# Sensors.net
KiCad netlist of a schematic drawn in Altium Designer
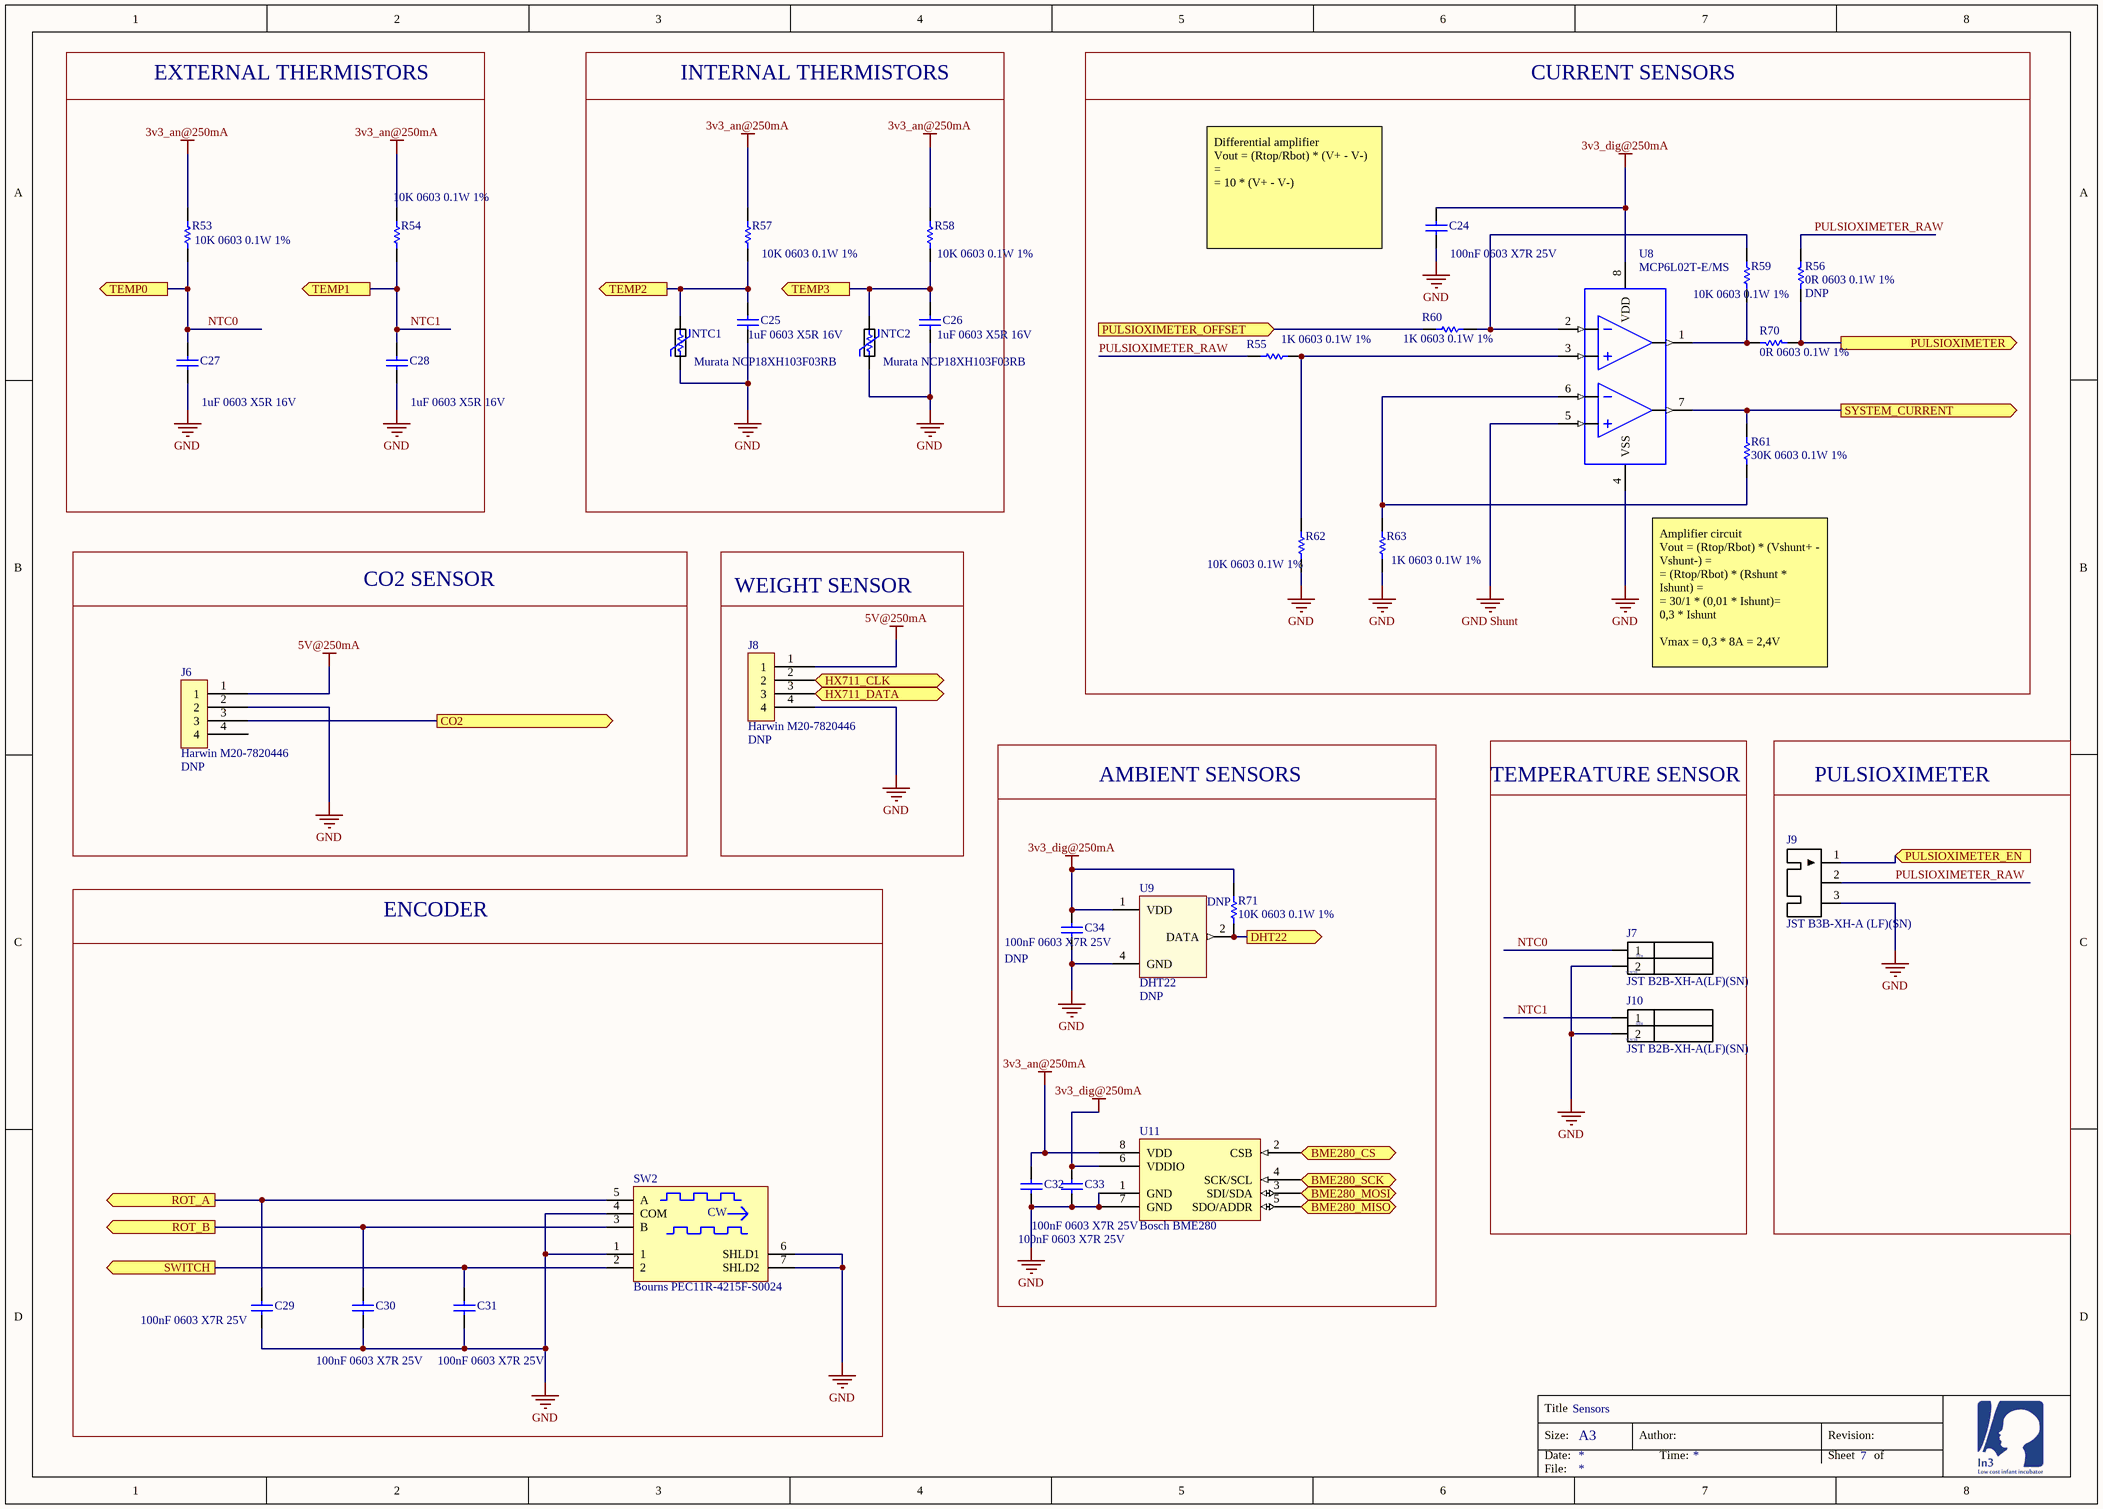
[diagram p0: Sensors.SchDoc]

(export (version "E")
  (design (tool "Eeschema 10.0.6"))
  (components
    (comp (ref "C24")
      (value "100nF 0603 X7R 25V")
      (footprint "CAPC1608X60X35NL10T15")
      (libsource (lib "CommunityVault") (part "CMP-c41a0d2b65641bdd-3"))
    )
    (comp (ref "C25")
      (value "1uF 0603 X5R 16V")
      (footprint "CAPC1608X60X35NL10T15")
      (fields (field (name "MANUFACTURER PART NUMBER") "GRM185R61C105KE44D"))
      (libsource (lib "CommunityVault") (part "CMP-119984-2"))
    )
    (comp (ref "C26")
      (value "1uF 0603 X5R 16V")
      (footprint "CAPC1608X60X35NL10T15")
      (fields (field (name "MANUFACTURER PART NUMBER") "GRM185R61C105KE44D"))
      (libsource (lib "CommunityVault") (part "CMP-119984-2"))
    )
    (comp (ref "C27")
      (value "1uF 0603 X5R 16V")
      (footprint "CAPC1608X60X35NL10T15")
      (fields (field (name "MANUFACTURER PART NUMBER") "GRM185R61C105KE44D"))
      (libsource (lib "CommunityVault") (part "CMP-119984-2"))
    )
    (comp (ref "C28")
      (value "1uF 0603 X5R 16V")
      (footprint "CAPC1608X60X35NL10T15")
      (fields (field (name "MANUFACTURER PART NUMBER") "GRM185R61C105KE44D"))
      (libsource (lib "CommunityVault") (part "CMP-119984-2"))
    )
    (comp (ref "C29")
      (value "100nF 0603 X7R 25V")
      (footprint "CAPC1608X60X35NL10T15")
      (libsource (lib "CommunityVault") (part "CMP-c41a0d2b65641bdd-3"))
    )
    (comp (ref "C30")
      (value "100nF 0603 X7R 25V")
      (footprint "CAPC1608X60X35NL10T15")
      (libsource (lib "CommunityVault") (part "CMP-c41a0d2b65641bdd-3"))
    )
    (comp (ref "C31")
      (value "100nF 0603 X7R 25V")
      (footprint "CAPC1608X60X35NL10T15")
      (libsource (lib "CommunityVault") (part "CMP-c41a0d2b65641bdd-3"))
    )
    (comp (ref "C32")
      (value "100nF 0603 X7R 25V")
      (footprint "CAPC1608X60X35NL10T15")
      (libsource (lib "CommunityVault") (part "CMP-c41a0d2b65641bdd-3"))
    )
    (comp (ref "C33")
      (value "100nF 0603 X7R 25V")
      (footprint "CAPC1608X60X35NL10T15")
      (libsource (lib "CommunityVault") (part "CMP-c41a0d2b65641bdd-3"))
    )
    (comp (ref "C34")
      (value "100nF 0603 X7R 25V")
      (footprint "CAPC1608X60X35NL10T15")
      (fields (field (name "DNP") "DNP"))
      (libsource (lib "CommunityVault") (part "CMP-c41a0d2b65641bdd-3"))
    )
    (comp (ref "J6")
      (value "Harwin M20-7820446")
      (footprint "PCB-tt6oa92k1i3euqam155k-1")
      (description "Conn Socket Strip SKT 4 POS 2.54mm Solder ST Thru-Hole Tube")
      (fields (field (name "MANUFACTURER PART NUMBER") "M20-7820446") (field (name "DNP") "DNP"))
      (libsource (lib "CommunityVault") (part "CMP-2481958-5"))
    )
    (comp (ref "J7")
      (value "JST B2B-XH-A(LF)(SN)")
      (footprint "PCB-fq0z2oxaey6bitejv126-1")
      (description "XH Series 2 Position 2.5 mm Pitch Through Hole Top Entry Shrouded Header")
      (fields (field (name "MANUFACTURER PART NUMBER") "B2B-XH-A(LF)(SN)"))
      (libsource (lib "CommunityVault") (part "CMP-2317ea6c4d2dfcd0-16"))
    )
    (comp (ref "J8")
      (value "Harwin M20-7820446")
      (footprint "PCB-tt6oa92k1i3euqam155k-1")
      (description "Conn Socket Strip SKT 4 POS 2.54mm Solder ST Thru-Hole Tube")
      (fields (field (name "MANUFACTURER PART NUMBER") "M20-7820446") (field (name "DNP") "DNP"))
      (libsource (lib "CommunityVault") (part "CMP-2481958-5"))
    )
    (comp (ref "J9")
      (value "JST B3B-XH-A (LF)(SN)")
      (footprint "PCB-sw29re0t3wmdwksqqhzo-1")
      (description "XH Series 3 Position 2.5 mm Pitch Through Hole Crimp Top Entry Shrouded Header")
      (libsource (lib "CommunityVault") (part "SYM-56379f4f046d89f0-1"))
    )
    (comp (ref "J10")
      (value "JST B2B-XH-A(LF)(SN)")
      (footprint "PCB-fq0z2oxaey6bitejv126-1")
      (description "XH Series 2 Position 2.5 mm Pitch Through Hole Top Entry Shrouded Header")
      (fields (field (name "MANUFACTURER PART NUMBER") "B2B-XH-A(LF)(SN)"))
      (libsource (lib "CommunityVault") (part "CMP-2317ea6c4d2dfcd0-16"))
    )
    (comp (ref "NTC1")
      (value "Murata NCP18XH103F03RB")
      (footprint "RESC1609X55X30ML10T20")
      (description "Thermistor NTC 10K Ohm 1% 2-Pin 0603 Surface Mount Solder Pad 3434K T/R")
      (fields (field (name "MANUFACTURER PART NUMBER") "NCP18XH103F03RB") (field (name "TOLERANCE") "1%"))
      (libsource (lib "CommunityVault") (part "CMP-2153918-5"))
    )
    (comp (ref "NTC2")
      (value "Murata NCP18XH103F03RB")
      (footprint "RESC1609X55X30ML10T20")
      (description "Thermistor NTC 10K Ohm 1% 2-Pin 0603 Surface Mount Solder Pad 3434K T/R")
      (fields (field (name "MANUFACTURER PART NUMBER") "NCP18XH103F03RB") (field (name "TOLERANCE") "1%"))
      (libsource (lib "CommunityVault") (part "CMP-2153918-5"))
    )
    (comp (ref "R53")
      (value "10K 0603 0.1W 1%")
      (footprint "RESC1609X55X30ML10T20")
      (fields (field (name "TOLERANCE") "1%"))
      (libsource (lib "CommunityVault") (part "CMP-4716590-9"))
    )
    (comp (ref "R54")
      (value "10K 0603 0.1W 1%")
      (footprint "RESC1609X55X30ML10T20")
      (fields (field (name "TOLERANCE") "1%"))
      (libsource (lib "CommunityVault") (part "CMP-4716590-9"))
    )
    (comp (ref "R55")
      (value "1K 0603 0.1W 1%")
      (footprint "RESC1609X55X30ML10T20")
      (fields (field (name "MANUFACTURER PART NUMBER") "CR0603-FX-1001ELF"))
      (libsource (lib "CommunityVault") (part "CMP-a61f6f36030f79d8-4"))
    )
    (comp (ref "R56")
      (value "0R 0603 0.1W 1%")
      (footprint "RESC1609X55X30ML10T20")
      (fields (field (name "DNP") "DNP"))
      (libsource (lib "CommunityVault") (part "CMP-536b9a7387ce8cac-10"))
    )
    (comp (ref "R57")
      (value "10K 0603 0.1W 1%")
      (footprint "RESC1609X55X30ML10T20")
      (fields (field (name "TOLERANCE") "1%"))
      (libsource (lib "CommunityVault") (part "CMP-4716590-9"))
    )
    (comp (ref "R58")
      (value "10K 0603 0.1W 1%")
      (footprint "RESC1609X55X30ML10T20")
      (fields (field (name "TOLERANCE") "1%"))
      (libsource (lib "CommunityVault") (part "CMP-4716590-9"))
    )
    (comp (ref "R59")
      (value "10K 0603 0.1W 1%")
      (footprint "RESC1609X55X30ML10T20")
      (fields (field (name "TOLERANCE") "1%"))
      (libsource (lib "CommunityVault") (part "CMP-4716590-9"))
    )
    (comp (ref "R60")
      (value "1K 0603 0.1W 1%")
      (footprint "RESC1609X55X30ML10T20")
      (fields (field (name "MANUFACTURER PART NUMBER") "CR0603-FX-1001ELF"))
      (libsource (lib "CommunityVault") (part "CMP-a61f6f36030f79d8-4"))
    )
    (comp (ref "R61")
      (value "30K 0603 0.1W 1%")
      (footprint "RESC1609X55X30ML10T20")
      (fields (field (name "TOLERANCE") "1%"))
      (libsource (lib "CommunityVault") (part "CMP-3655986-6"))
    )
    (comp (ref "R62")
      (value "10K 0603 0.1W 1%")
      (footprint "RESC1609X55X30ML10T20")
      (fields (field (name "TOLERANCE") "1%"))
      (libsource (lib "CommunityVault") (part "CMP-4716590-9"))
    )
    (comp (ref "R63")
      (value "1K 0603 0.1W 1%")
      (footprint "RESC1609X55X30ML10T20")
      (fields (field (name "MANUFACTURER PART NUMBER") "CR0603-FX-1001ELF"))
      (libsource (lib "CommunityVault") (part "CMP-a61f6f36030f79d8-4"))
    )
    (comp (ref "R70")
      (value "0R 0603 0.1W 1%")
      (footprint "RESC1609X55X30ML10T20")
      (libsource (lib "CommunityVault") (part "CMP-536b9a7387ce8cac-10"))
    )
    (comp (ref "R71")
      (value "10K 0603 0.1W 1%")
      (footprint "RESC1609X55X30ML10T20")
      (fields (field (name "TOLERANCE") "1%") (field (name "DNP") "DNP"))
      (libsource (lib "CommunityVault") (part "CMP-4716590-9"))
    )
    (comp (ref "SW2")
      (value "Bourns PEC11R-4215F-S0024")
      (footprint "BOUR-PEC11R-4XXXF-SXXXX_V")
      (description "12 mm Incremental Encoder, 24 Detent, -30 to 70 degC, 5-Pin THD, RoHS, Bulk")
      (fields (field (name "MANUFACTURER PART NUMBER") "PEC11R-4215F-S0024"))
      (libsource (lib "FavoritesLibrary") (part "SW-ENCODER-5"))
    )
    (comp (ref "U8")
      (value "MCP6L02T-E/MS")
      (footprint "PCB-e8n0jpjj0ctkgxf737qv-1")
      (description "Microchip MCP6L02T-E/MS, Dual Op Amp, 1MHz Rail-Rail, 1.8 to 6 V, 8-Pin MSOP")
      (libsource (lib "CommunityVault") (part "CMP-1319549-4"))
    )
    (comp (ref "U9")
      (value "DHT22")
      (footprint "DHT22")
      (description "Micrometer Head for Small Items, Opens to 1/2\", Compatible with all 300 Series Bases")
      (fields (field (name "MANUFACTURER PART NUMBER") "385") (field (name "DNP") "DNP"))
      (libsource (lib "CommunityVault") (part "CMP-ab3a63ff523b74fd-4"))
    )
    (comp (ref "U11")
      (value "Bosch BME280")
      (footprint "LGA-8")
      (description "Combined humidity and pressure sensor")
      (fields (field (name "MANUFACTURER PART NUMBER") "BME280"))
      (libsource (lib "CommunityVault") (part "SYM-19345792-1"))
    )
  )
  (nets
    (net (code "1") (name "/BME280_CS") (class "Default")
      (node (ref "U11") (pin "2") (pinfunction "CSB_2") (pintype "input"))
    )
    (net (code "2") (name "/BME280_MISO") (class "Default")
      (node (ref "U11") (pin "5") (pinfunction "SDO/ADDR_5") (pintype "bidirectional"))
    )
    (net (code "3") (name "/BME280_MOSI") (class "Default")
      (node (ref "U11") (pin "3") (pinfunction "SDI/SDA_3") (pintype "bidirectional"))
    )
    (net (code "4") (name "/BME280_SCK") (class "Default")
      (node (ref "U11") (pin "4") (pinfunction "SCK/SCL_4") (pintype "input"))
    )
    (net (code "5") (name "/CO2") (class "Default")
      (node (ref "J6") (pin "3") (pinfunction "3_3") (pintype "passive"))
    )
    (net (code "6") (name "/DHT22") (class "Default")
      (node (ref "R71") (pin "2") (pinfunction "2_2") (pintype "passive"))
      (node (ref "U9") (pin "2") (pinfunction "DATA_2") (pintype "output"))
    )
    (net (code "7") (name "/HX711_CLK") (class "Default")
      (node (ref "J8") (pin "2") (pinfunction "2_2") (pintype "passive"))
    )
    (net (code "8") (name "/HX711_DATA") (class "Default")
      (node (ref "J8") (pin "3") (pinfunction "3_3") (pintype "passive"))
    )
    (net (code "9") (name "/NTC0") (class "Default")
      (node (ref "C27") (pin "1") (pinfunction "1_1") (pintype "passive"))
      (node (ref "J7") (pin "1") (pinfunction "1_1") (pintype "passive"))
      (node (ref "R53") (pin "1") (pinfunction "1_1") (pintype "passive"))
    )
    (net (code "10") (name "/NTC1") (class "Default")
      (node (ref "C28") (pin "1") (pinfunction "1_1") (pintype "passive"))
      (node (ref "J10") (pin "1") (pinfunction "1_1") (pintype "passive"))
      (node (ref "R54") (pin "1") (pinfunction "1_1") (pintype "passive"))
    )
    (net (code "11") (name "/PULSIOXIMETER") (class "Default")
      (node (ref "R56") (pin "1") (pinfunction "1_1") (pintype "passive"))
      (node (ref "R70") (pin "1") (pinfunction "1_1") (pintype "passive"))
    )
    (net (code "12") (name "/PULSIOXIMETER_EN") (class "Default")
      (node (ref "J9") (pin "1") (pinfunction "1_1") (pintype "passive"))
    )
    (net (code "13") (name "/PULSIOXIMETER_OFFSET") (class "Default")
      (node (ref "R60") (pin "1") (pinfunction "1_1") (pintype "passive"))
    )
    (net (code "14") (name "/PULSIOXIMETER_RAW") (class "Default")
      (node (ref "J9") (pin "2") (pinfunction "2_2") (pintype "passive"))
      (node (ref "R55") (pin "1") (pinfunction "1_1") (pintype "passive"))
      (node (ref "R56") (pin "2") (pinfunction "2_2") (pintype "passive"))
    )
    (net (code "15") (name "/ROT_A") (class "Default")
      (node (ref "C29") (pin "2") (pinfunction "2_2") (pintype "passive"))
      (node (ref "SW2") (pin "5") (pinfunction "A_5") (pintype "passive"))
    )
    (net (code "16") (name "/ROT_B") (class "Default")
      (node (ref "C30") (pin "2") (pinfunction "2_2") (pintype "passive"))
      (node (ref "SW2") (pin "3") (pinfunction "B_3") (pintype "passive"))
    )
    (net (code "17") (name "/SWITCH") (class "Default")
      (node (ref "C31") (pin "2") (pinfunction "2_2") (pintype "passive"))
      (node (ref "SW2") (pin "2") (pinfunction "2_2") (pintype "passive"))
    )
    (net (code "18") (name "/SYSTEM_CURRENT") (class "Default")
      (node (ref "R61") (pin "1") (pinfunction "1_1") (pintype "passive"))
      (node (ref "U8") (pin "7") (pinfunction "OUT_B_7") (pintype "output"))
    )
    (net (code "19") (name "/TEMP2") (class "Default")
      (node (ref "C25") (pin "1") (pinfunction "1_1") (pintype "passive"))
      (node (ref "NTC1") (pin "2") (pinfunction "2_2") (pintype "passive"))
      (node (ref "R57") (pin "1") (pinfunction "1_1") (pintype "passive"))
    )
    (net (code "20") (name "/TEMP3") (class "Default")
      (node (ref "C26") (pin "1") (pinfunction "1_1") (pintype "passive"))
      (node (ref "NTC2") (pin "2") (pinfunction "2_2") (pintype "passive"))
      (node (ref "R58") (pin "1") (pinfunction "1_1") (pintype "passive"))
    )
    (net (code "21") (name "3v3_an@250mA") (class "Default")
      (node (ref "C32") (pin "2") (pinfunction "2_2") (pintype "passive"))
      (node (ref "R53") (pin "2") (pinfunction "2_2") (pintype "passive"))
      (node (ref "R54") (pin "2") (pinfunction "2_2") (pintype "passive"))
      (node (ref "R57") (pin "2") (pinfunction "2_2") (pintype "passive"))
      (node (ref "R58") (pin "2") (pinfunction "2_2") (pintype "passive"))
      (node (ref "U11") (pin "8") (pinfunction "VDD_8") (pintype "power_in"))
    )
    (net (code "22") (name "3v3_dig@250mA") (class "Default")
      (node (ref "C24") (pin "2") (pinfunction "2_2") (pintype "passive"))
      (node (ref "C33") (pin "2") (pinfunction "2_2") (pintype "passive"))
      (node (ref "C34") (pin "2") (pinfunction "2_2") (pintype "passive"))
      (node (ref "R71") (pin "1") (pinfunction "1_1") (pintype "passive"))
      (node (ref "U11") (pin "6") (pinfunction "VDDIO_6") (pintype "power_in"))
      (node (ref "U8") (pin "8") (pinfunction "VDD_8") (pintype "power_in"))
      (node (ref "U9") (pin "1") (pinfunction "VDD_1") (pintype "power_in"))
    )
    (net (code "23") (name "5V@250mA") (class "Default")
      (node (ref "J6") (pin "1") (pinfunction "1_1") (pintype "passive"))
      (node (ref "J8") (pin "1") (pinfunction "1_1") (pintype "passive"))
    )
    (net (code "24") (name "GND") (class "Default")
      (node (ref "C24") (pin "1") (pinfunction "1_1") (pintype "passive"))
      (node (ref "C25") (pin "2") (pinfunction "2_2") (pintype "passive"))
      (node (ref "C26") (pin "2") (pinfunction "2_2") (pintype "passive"))
      (node (ref "C27") (pin "2") (pinfunction "2_2") (pintype "passive"))
      (node (ref "C28") (pin "2") (pinfunction "2_2") (pintype "passive"))
      (node (ref "C29") (pin "1") (pinfunction "1_1") (pintype "passive"))
      (node (ref "C30") (pin "1") (pinfunction "1_1") (pintype "passive"))
      (node (ref "C31") (pin "1") (pinfunction "1_1") (pintype "passive"))
      (node (ref "C32") (pin "1") (pinfunction "1_1") (pintype "passive"))
      (node (ref "C33") (pin "1") (pinfunction "1_1") (pintype "passive"))
      (node (ref "C34") (pin "1") (pinfunction "1_1") (pintype "passive"))
      (node (ref "J10") (pin "2") (pinfunction "2_2") (pintype "passive"))
      (node (ref "J6") (pin "2") (pinfunction "2_2") (pintype "passive"))
      (node (ref "J7") (pin "2") (pinfunction "2_2") (pintype "passive"))
      (node (ref "J8") (pin "4") (pinfunction "4_4") (pintype "passive"))
      (node (ref "J9") (pin "3") (pinfunction "3_3") (pintype "passive"))
      (node (ref "NTC1") (pin "1") (pinfunction "1_1") (pintype "passive"))
      (node (ref "NTC2") (pin "1") (pinfunction "1_1") (pintype "passive"))
      (node (ref "R62") (pin "1") (pinfunction "1_1") (pintype "passive"))
      (node (ref "R63") (pin "1") (pinfunction "1_1") (pintype "passive"))
      (node (ref "SW2") (pin "1") (pinfunction "1_1") (pintype "passive"))
      (node (ref "SW2") (pin "4") (pinfunction "COM_4") (pintype "passive"))
      (node (ref "SW2") (pin "6") (pinfunction "SHLD1_6") (pintype "passive"))
      (node (ref "SW2") (pin "7") (pinfunction "SHLD2_7") (pintype "passive"))
      (node (ref "U11") (pin "1") (pinfunction "GND_1") (pintype "power_in"))
      (node (ref "U11") (pin "7") (pinfunction "GND_7") (pintype "power_in"))
      (node (ref "U8") (pin "4") (pinfunction "VSS_4") (pintype "power_in"))
      (node (ref "U9") (pin "4") (pinfunction "GND_4") (pintype "power_in"))
    )
    (net (code "25") (name "GND Shunt") (class "Default")
      (node (ref "U8") (pin "5") (pinfunction "VINB+_5") (pintype "input"))
    )
    (net (code "26") (name "Net-(U8-VINA+)") (class "Default")
      (node (ref "R55") (pin "2") (pinfunction "2_2") (pintype "passive"))
      (node (ref "R62") (pin "2") (pinfunction "2_2") (pintype "passive"))
      (node (ref "U8") (pin "3") (pinfunction "VINA+_3") (pintype "input"))
    )
    (net (code "27") (name "Net-(U8-VINA-)") (class "Default")
      (node (ref "R59") (pin "2") (pinfunction "2_2") (pintype "passive"))
      (node (ref "R60") (pin "2") (pinfunction "2_2") (pintype "passive"))
      (node (ref "U8") (pin "2") (pinfunction "VINA-_2") (pintype "input"))
    )
    (net (code "28") (name "Net-(U8-VINB-)") (class "Default")
      (node (ref "R61") (pin "2") (pinfunction "2_2") (pintype "passive"))
      (node (ref "R63") (pin "2") (pinfunction "2_2") (pintype "passive"))
      (node (ref "U8") (pin "6") (pinfunction "VINB-_6") (pintype "input"))
    )
    (net (code "29") (name "Net-(U8-VOUTA)") (class "Default")
      (node (ref "R59") (pin "1") (pinfunction "1_1") (pintype "passive"))
      (node (ref "R70") (pin "2") (pinfunction "2_2") (pintype "passive"))
      (node (ref "U8") (pin "1") (pinfunction "VOUTA_1") (pintype "output"))
    )
    (net (code "30") (name "unconnected-(J6-Pad4)") (class "Default")
      (node (ref "J6") (pin "4") (pinfunction "4_4") (pintype "passive"))
    )
  )
)
